# Sheet3.net
KiCad netlist of a schematic drawn in Altium Designer
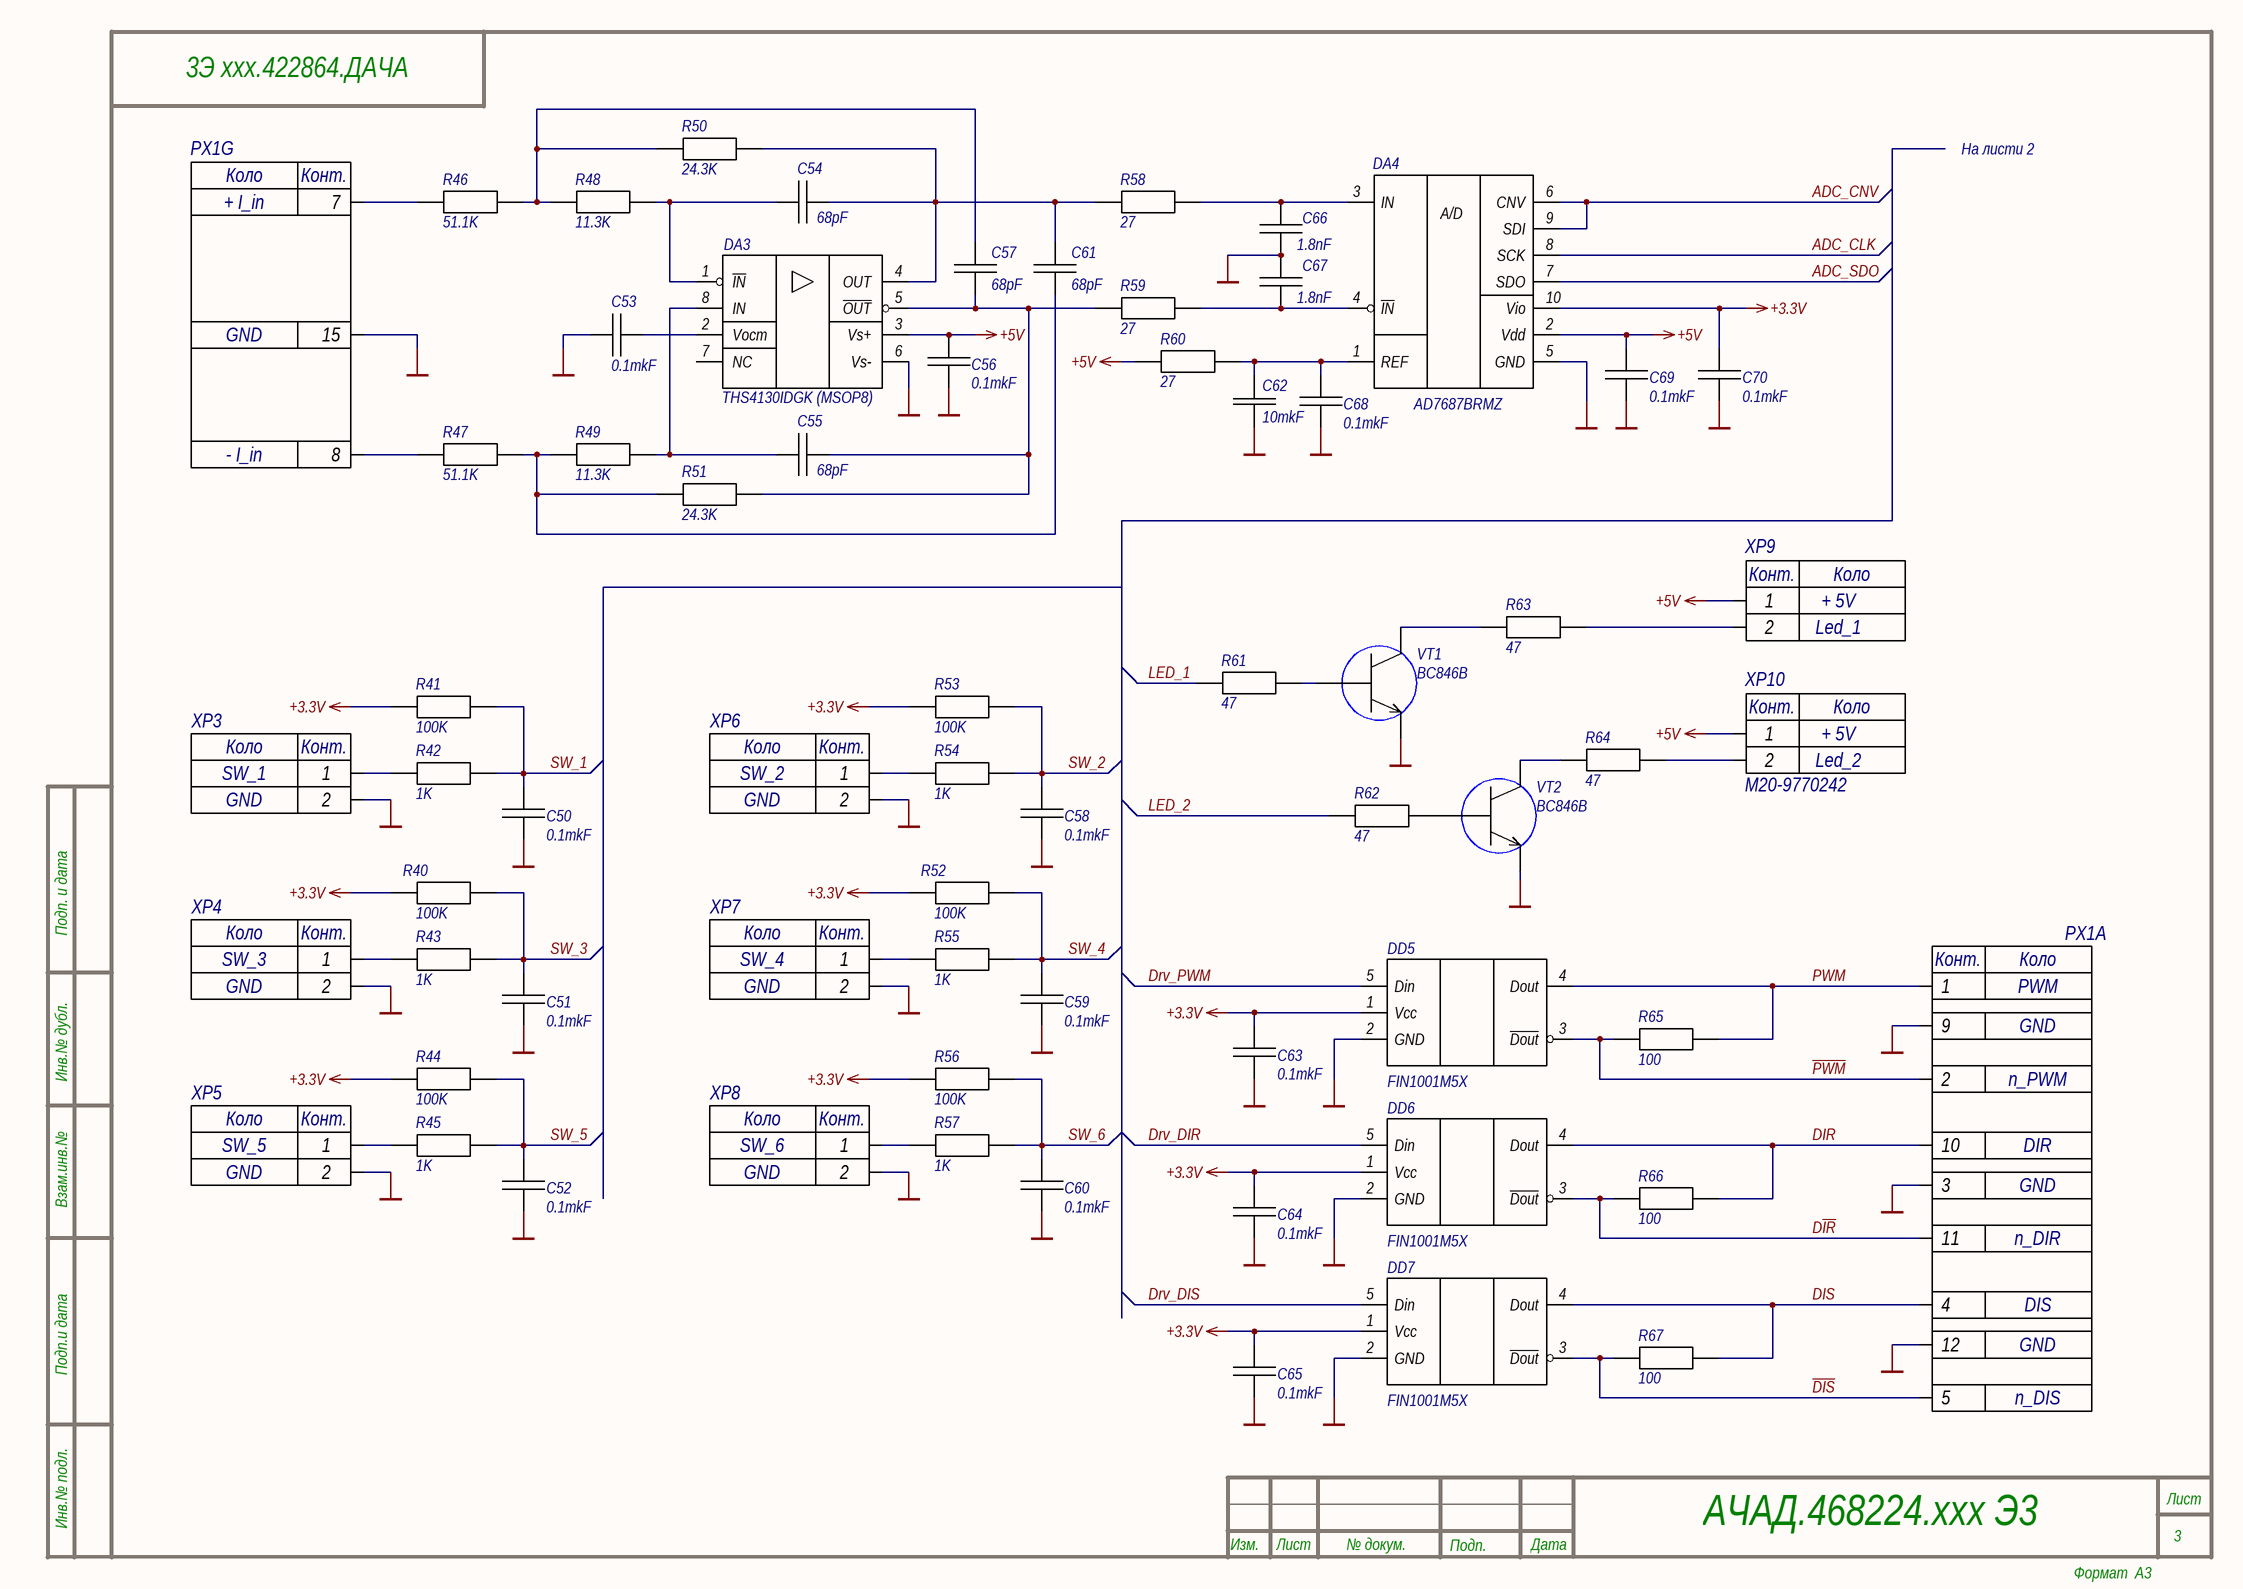
[diagram p0: Sheet3.SchDoc]

(export (version "E")
  (design (tool "Eeschema 10.0.6"))
  (components
    (comp (ref "C50")
      (value "0.1mkF")
      (footprint "C_0603")
      (description "C_0.1mkF_0603")
      (libsource (lib "АСК_1") (part "C_0.1mkF_0603"))
    )
    (comp (ref "C51")
      (value "0.1mkF")
      (footprint "C_0603")
      (description "C_0.1mkF_0603")
      (libsource (lib "АСК_1") (part "C_0.1mkF_0603"))
    )
    (comp (ref "C52")
      (value "0.1mkF")
      (footprint "C_0603")
      (description "C_0.1mkF_0603")
      (libsource (lib "АСК_1") (part "C_0.1mkF_0603"))
    )
    (comp (ref "C53")
      (value "0.1mkF")
      (footprint "C_0603")
      (description "C_0.1mkF_0603")
      (libsource (lib "АСК_1") (part "C_0.1mkF_0603"))
    )
    (comp (ref "C54")
      (value "68pF")
      (footprint "C_0603")
      (description "C_0.1mkF_0603")
      (libsource (lib "АСК_1") (part "C_0.1mkF_0603"))
    )
    (comp (ref "C55")
      (value "68pF")
      (footprint "C_0603")
      (description "C_0.1mkF_0603")
      (libsource (lib "АСК_1") (part "C_0.1mkF_0603"))
    )
    (comp (ref "C56")
      (value "0.1mkF")
      (footprint "C_0603")
      (description "C_0.1mkF_0603")
      (libsource (lib "АСК_1") (part "C_0.1mkF_0603"))
    )
    (comp (ref "C57")
      (value "68pF")
      (footprint "C_0603")
      (description "C_0.1mkF_0603")
      (libsource (lib "АСК_1") (part "C_0.1mkF_0603"))
    )
    (comp (ref "C58")
      (value "0.1mkF")
      (footprint "C_0603")
      (description "C_0.1mkF_0603")
      (libsource (lib "АСК_1") (part "C_0.1mkF_0603"))
    )
    (comp (ref "C59")
      (value "0.1mkF")
      (footprint "C_0603")
      (description "C_0.1mkF_0603")
      (libsource (lib "АСК_1") (part "C_0.1mkF_0603"))
    )
    (comp (ref "C60")
      (value "0.1mkF")
      (footprint "C_0603")
      (description "C_0.1mkF_0603")
      (libsource (lib "АСК_1") (part "C_0.1mkF_0603"))
    )
    (comp (ref "C61")
      (value "68pF")
      (footprint "C_0603")
      (description "C_0.1mkF_0603")
      (libsource (lib "АСК_1") (part "C_0.1mkF_0603"))
    )
    (comp (ref "C62")
      (value "10mkF")
      (footprint "C_1206")
      (description "C_10mkF_1206")
      (libsource (lib "АСК_1") (part "C_10mkF_1206"))
    )
    (comp (ref "C63")
      (value "0.1mkF")
      (footprint "C_0603")
      (description "C_0.1mkF_0603")
      (libsource (lib "АСК_1") (part "C_0.1mkF_0603"))
    )
    (comp (ref "C64")
      (value "0.1mkF")
      (footprint "C_0603")
      (description "C_0.1mkF_0603")
      (libsource (lib "АСК_1") (part "C_0.1mkF_0603"))
    )
    (comp (ref "C65")
      (value "0.1mkF")
      (footprint "C_0603")
      (description "C_0.1mkF_0603")
      (libsource (lib "АСК_1") (part "C_0.1mkF_0603"))
    )
    (comp (ref "C66")
      (value "1.8nF")
      (footprint "C_0603")
      (description "C_0.1mkF_0603")
      (libsource (lib "АСК_1") (part "C_0.1mkF_0603"))
    )
    (comp (ref "C67")
      (value "1.8nF")
      (footprint "C_0603")
      (description "C_0.1mkF_0603")
      (libsource (lib "АСК_1") (part "C_0.1mkF_0603"))
    )
    (comp (ref "C68")
      (value "0.1mkF")
      (footprint "C_0603")
      (description "C_0.1mkF_0603")
      (libsource (lib "АСК_1") (part "C_0.1mkF_0603"))
    )
    (comp (ref "C69")
      (value "0.1mkF")
      (footprint "C_0603")
      (description "C_0.1mkF_0603")
      (libsource (lib "АСК_1") (part "C_0.1mkF_0603"))
    )
    (comp (ref "C70")
      (value "0.1mkF")
      (footprint "C_0603")
      (description "C_0.1mkF_0603")
      (libsource (lib "АСК_1") (part "C_0.1mkF_0603"))
    )
    (comp (ref "DA3")
      (value "THS4130IDGK (MSOP8)")
      (footprint "THS4130IDGK(MSOP8)")
      (libsource (lib "АСК_1") (part "THS4130IDGK (MSOP8)"))
    )
    (comp (ref "DA4") (value "AD7687BRMZ") (libsource (lib "АСК_1") (part "AD7687BRMZ")))
    (comp (ref "DD5") (value "FIN1001M5X") (libsource (lib "АСК_1") (part "FIN1001M5X")))
    (comp (ref "DD6") (value "FIN1001M5X") (libsource (lib "АСК_1") (part "FIN1001M5X")))
    (comp (ref "DD7") (value "FIN1001M5X") (libsource (lib "АСК_1") (part "FIN1001M5X")))
    (comp (ref "PX1") (value "DB_15") (libsource (lib "АСК_1") (part "DB_15")))
    (comp (ref "R40")
      (value "100K")
      (footprint "R_0603")
      (description "R_100_0603")
      (libsource (lib "АСК_1") (part "R_100_0603"))
    )
    (comp (ref "R41")
      (value "100K")
      (footprint "R_0603")
      (description "R_100_0603")
      (libsource (lib "АСК_1") (part "R_100_0603"))
    )
    (comp (ref "R42")
      (value "1K")
      (footprint "R_0603")
      (description "R_100_0603")
      (libsource (lib "АСК_1") (part "R_100_0603"))
    )
    (comp (ref "R43")
      (value "1K")
      (footprint "R_0603")
      (description "R_100_0603")
      (libsource (lib "АСК_1") (part "R_100_0603"))
    )
    (comp (ref "R44")
      (value "100K")
      (footprint "R_0603")
      (description "R_100_0603")
      (libsource (lib "АСК_1") (part "R_100_0603"))
    )
    (comp (ref "R45")
      (value "1K")
      (footprint "R_0603")
      (description "R_100_0603")
      (libsource (lib "АСК_1") (part "R_100_0603"))
    )
    (comp (ref "R46")
      (value "51.1K")
      (footprint "R_0603")
      (description "R_100_0603")
      (libsource (lib "АСК_1") (part "R_100_0603"))
    )
    (comp (ref "R47")
      (value "51.1K")
      (footprint "R_0603")
      (description "R_100_0603")
      (libsource (lib "АСК_1") (part "R_100_0603"))
    )
    (comp (ref "R48")
      (value "11.3K")
      (footprint "R_0603")
      (description "R_100_0603")
      (libsource (lib "АСК_1") (part "R_100_0603"))
    )
    (comp (ref "R49")
      (value "11.3K")
      (footprint "R_0603")
      (description "R_100_0603")
      (libsource (lib "АСК_1") (part "R_100_0603"))
    )
    (comp (ref "R50")
      (value "24.3K")
      (footprint "R_0603")
      (description "R_100_0603")
      (libsource (lib "АСК_1") (part "R_100_0603"))
    )
    (comp (ref "R51")
      (value "24.3K")
      (footprint "R_0603")
      (description "R_100_0603")
      (libsource (lib "АСК_1") (part "R_100_0603"))
    )
    (comp (ref "R52")
      (value "100K")
      (footprint "R_0603")
      (description "R_100_0603")
      (libsource (lib "АСК_1") (part "R_100_0603"))
    )
    (comp (ref "R53")
      (value "100K")
      (footprint "R_0603")
      (description "R_100_0603")
      (libsource (lib "АСК_1") (part "R_100_0603"))
    )
    (comp (ref "R54")
      (value "1K")
      (footprint "R_0603")
      (description "R_100_0603")
      (libsource (lib "АСК_1") (part "R_100_0603"))
    )
    (comp (ref "R55")
      (value "1K")
      (footprint "R_0603")
      (description "R_100_0603")
      (libsource (lib "АСК_1") (part "R_100_0603"))
    )
    (comp (ref "R56")
      (value "100K")
      (footprint "R_0603")
      (description "R_100_0603")
      (libsource (lib "АСК_1") (part "R_100_0603"))
    )
    (comp (ref "R57")
      (value "1K")
      (footprint "R_0603")
      (description "R_100_0603")
      (libsource (lib "АСК_1") (part "R_100_0603"))
    )
    (comp (ref "R58")
      (value "27")
      (footprint "R_0603")
      (description "R_100_0603")
      (libsource (lib "АСК_1") (part "R_100_0603"))
    )
    (comp (ref "R59")
      (value "27")
      (footprint "R_0603")
      (description "R_100_0603")
      (libsource (lib "АСК_1") (part "R_100_0603"))
    )
    (comp (ref "R60")
      (value "27")
      (footprint "R_0603")
      (description "R_100_0603")
      (libsource (lib "АСК_1") (part "R_100_0603"))
    )
    (comp (ref "R61")
      (value "47")
      (footprint "R_0603")
      (description "R_100_0603")
      (libsource (lib "АСК_1") (part "R_100_0603"))
    )
    (comp (ref "R62")
      (value "47")
      (footprint "R_0603")
      (description "R_100_0603")
      (libsource (lib "АСК_1") (part "R_100_0603"))
    )
    (comp (ref "R63")
      (value "47")
      (footprint "R_0603")
      (description "R_100_0603")
      (libsource (lib "АСК_1") (part "R_100_0603"))
    )
    (comp (ref "R64")
      (value "47")
      (footprint "R_0603")
      (description "R_100_0603")
      (libsource (lib "АСК_1") (part "R_100_0603"))
    )
    (comp (ref "R65")
      (value "100")
      (footprint "R_0603")
      (description "R_100_0603")
      (libsource (lib "АСК_1") (part "R_100_0603"))
    )
    (comp (ref "R66")
      (value "100")
      (footprint "R_0603")
      (description "R_100_0603")
      (libsource (lib "АСК_1") (part "R_100_0603"))
    )
    (comp (ref "R67")
      (value "100")
      (footprint "R_0603")
      (description "R_100_0603")
      (libsource (lib "АСК_1") (part "R_100_0603"))
    )
    (comp (ref "VT1")
      (value "BC846B")
      (footprint "SOT95P245X110 3N")
      (libsource (lib "АСК_1") (part "BC846B"))
    )
    (comp (ref "VT2")
      (value "BC846B")
      (footprint "SOT95P245X110 3N")
      (libsource (lib "АСК_1") (part "BC846B"))
    )
    (comp (ref "XP3") (value "M20-9770242") (libsource (lib "АСК_1") (part "M20-9770242")))
    (comp (ref "XP4") (value "M20-9770242") (libsource (lib "АСК_1") (part "M20-9770242")))
    (comp (ref "XP5") (value "M20-9770242") (libsource (lib "АСК_1") (part "M20-9770242")))
    (comp (ref "XP6") (value "M20-9770242") (libsource (lib "АСК_1") (part "M20-9770242")))
    (comp (ref "XP7") (value "M20-9770242") (libsource (lib "АСК_1") (part "M20-9770242")))
    (comp (ref "XP8") (value "M20-9770242") (libsource (lib "АСК_1") (part "M20-9770242")))
    (comp (ref "XP9") (value "M20-9770242") (libsource (lib "АСК_1") (part "M20-9770242")))
    (comp (ref "XP10") (value "M20-9770242") (libsource (lib "АСК_1") (part "M20-9770242")))
  )
  (nets
    (net (code "1") (name "+3.3V") (class "Default")
      (node (ref "C63") (pin "1") (pinfunction "1_1") (pintype "passive"))
      (node (ref "C64") (pin "1") (pinfunction "1_1") (pintype "passive"))
      (node (ref "C65") (pin "1") (pinfunction "1_1") (pintype "passive"))
      (node (ref "C70") (pin "1") (pinfunction "1_1") (pintype "passive"))
      (node (ref "DA4") (pin "10") (pinfunction "Vio_10") (pintype "passive"))
      (node (ref "DD5") (pin "1") (pinfunction "Vcc_1") (pintype "passive"))
      (node (ref "DD6") (pin "1") (pinfunction "Vcc_1") (pintype "passive"))
      (node (ref "DD7") (pin "1") (pinfunction "Vcc_1") (pintype "passive"))
      (node (ref "R40") (pin "1") (pinfunction "1_1") (pintype "passive"))
      (node (ref "R41") (pin "1") (pinfunction "1_1") (pintype "passive"))
      (node (ref "R44") (pin "1") (pinfunction "1_1") (pintype "passive"))
      (node (ref "R52") (pin "1") (pinfunction "1_1") (pintype "passive"))
      (node (ref "R53") (pin "1") (pinfunction "1_1") (pintype "passive"))
      (node (ref "R56") (pin "1") (pinfunction "1_1") (pintype "passive"))
    )
    (net (code "2") (name "+5V") (class "Default")
      (node (ref "C56") (pin "1") (pinfunction "1_1") (pintype "passive"))
      (node (ref "C69") (pin "1") (pinfunction "1_1") (pintype "passive"))
      (node (ref "DA3") (pin "3") (pinfunction "Vs+_3") (pintype "passive"))
      (node (ref "DA4") (pin "2") (pinfunction "Vdd_2") (pintype "passive"))
      (node (ref "R60") (pin "1") (pinfunction "1_1") (pintype "passive"))
      (node (ref "XP10") (pin "1") (pinfunction "1_1") (pintype "passive"))
      (node (ref "XP9") (pin "1") (pinfunction "1_1") (pintype "passive"))
    )
    (net (code "3") (name "/ADC_CLK") (class "Default")
      (node (ref "DA4") (pin "8") (pinfunction "SCK_8") (pintype "passive"))
    )
    (net (code "4") (name "/ADC_CNV") (class "Default")
      (node (ref "DA4") (pin "6") (pinfunction "CNV_6") (pintype "passive"))
      (node (ref "DA4") (pin "9") (pinfunction "SDI_9") (pintype "passive"))
    )
    (net (code "5") (name "/ADC_SDO") (class "Default")
      (node (ref "DA4") (pin "7") (pinfunction "SDO_7") (pintype "passive"))
    )
    (net (code "6") (name "/DIR") (class "Default")
      (node (ref "DD6") (pin "4") (pinfunction "Dout_4") (pintype "passive"))
      (node (ref "PX1") (pin "10") (pinfunction "10_10") (pintype "passive"))
      (node (ref "R66") (pin "2") (pinfunction "2_2") (pintype "passive"))
    )
    (net (code "7") (name "/DIS") (class "Default")
      (node (ref "DD7") (pin "4") (pinfunction "Dout_4") (pintype "passive"))
      (node (ref "PX1") (pin "4") (pinfunction "4_4") (pintype "passive"))
      (node (ref "R67") (pin "2") (pinfunction "2_2") (pintype "passive"))
    )
    (net (code "8") (name "/Drv_DIR") (class "Default")
      (node (ref "DD6") (pin "5") (pinfunction "Din_5") (pintype "passive"))
    )
    (net (code "9") (name "/Drv_DIS") (class "Default")
      (node (ref "DD7") (pin "5") (pinfunction "Din_5") (pintype "passive"))
    )
    (net (code "10") (name "/Drv_PWM") (class "Default")
      (node (ref "DD5") (pin "5") (pinfunction "Din_5") (pintype "passive"))
    )
    (net (code "11") (name "/D~{IR}") (class "Default")
      (node (ref "DD6") (pin "3") (pinfunction "~{Dout}_3") (pintype "passive"))
      (node (ref "PX1") (pin "11") (pinfunction "11_11") (pintype "passive"))
      (node (ref "R66") (pin "1") (pinfunction "1_1") (pintype "passive"))
    )
    (net (code "12") (name "/LED_1") (class "Default")
      (node (ref "R61") (pin "1") (pinfunction "1_1") (pintype "passive"))
    )
    (net (code "13") (name "/LED_2") (class "Default")
      (node (ref "R62") (pin "1") (pinfunction "1_1") (pintype "passive"))
    )
    (net (code "14") (name "/PWM") (class "Default")
      (node (ref "DD5") (pin "4") (pinfunction "Dout_4") (pintype "passive"))
      (node (ref "PX1") (pin "1") (pinfunction "1_1") (pintype "passive"))
      (node (ref "R65") (pin "2") (pinfunction "2_2") (pintype "passive"))
    )
    (net (code "15") (name "/SW_1") (class "Default")
      (node (ref "C50") (pin "1") (pinfunction "1_1") (pintype "passive"))
      (node (ref "R41") (pin "2") (pinfunction "2_2") (pintype "passive"))
      (node (ref "R42") (pin "2") (pinfunction "2_2") (pintype "passive"))
    )
    (net (code "16") (name "/SW_2") (class "Default")
      (node (ref "C58") (pin "1") (pinfunction "1_1") (pintype "passive"))
      (node (ref "R53") (pin "2") (pinfunction "2_2") (pintype "passive"))
      (node (ref "R54") (pin "2") (pinfunction "2_2") (pintype "passive"))
    )
    (net (code "17") (name "/SW_3") (class "Default")
      (node (ref "C51") (pin "1") (pinfunction "1_1") (pintype "passive"))
      (node (ref "R40") (pin "2") (pinfunction "2_2") (pintype "passive"))
      (node (ref "R43") (pin "2") (pinfunction "2_2") (pintype "passive"))
    )
    (net (code "18") (name "/SW_4") (class "Default")
      (node (ref "C59") (pin "1") (pinfunction "1_1") (pintype "passive"))
      (node (ref "R52") (pin "2") (pinfunction "2_2") (pintype "passive"))
      (node (ref "R55") (pin "2") (pinfunction "2_2") (pintype "passive"))
    )
    (net (code "19") (name "/SW_5") (class "Default")
      (node (ref "C52") (pin "1") (pinfunction "1_1") (pintype "passive"))
      (node (ref "R44") (pin "2") (pinfunction "2_2") (pintype "passive"))
      (node (ref "R45") (pin "2") (pinfunction "2_2") (pintype "passive"))
    )
    (net (code "20") (name "/SW_6") (class "Default")
      (node (ref "C60") (pin "1") (pinfunction "1_1") (pintype "passive"))
      (node (ref "R56") (pin "2") (pinfunction "2_2") (pintype "passive"))
      (node (ref "R57") (pin "2") (pinfunction "2_2") (pintype "passive"))
    )
    (net (code "21") (name "/~{DIS}") (class "Default")
      (node (ref "DD7") (pin "3") (pinfunction "~{Dout}_3") (pintype "passive"))
      (node (ref "PX1") (pin "5") (pinfunction "5_5") (pintype "passive"))
      (node (ref "R67") (pin "1") (pinfunction "1_1") (pintype "passive"))
    )
    (net (code "22") (name "/~{PWM}") (class "Default")
      (node (ref "DD5") (pin "3") (pinfunction "~{Dout}_3") (pintype "passive"))
      (node (ref "PX1") (pin "1") (pinfunction "2_1") (pintype "passive"))
      (node (ref "R65") (pin "1") (pinfunction "1_1") (pintype "passive"))
    )
    (net (code "23") (name "GND") (class "Default")
      (node (ref "C50") (pin "2") (pinfunction "2_2") (pintype "passive"))
      (node (ref "C51") (pin "2") (pinfunction "2_2") (pintype "passive"))
      (node (ref "C52") (pin "2") (pinfunction "2_2") (pintype "passive"))
      (node (ref "C53") (pin "1") (pinfunction "1_1") (pintype "passive"))
      (node (ref "C56") (pin "2") (pinfunction "2_2") (pintype "passive"))
      (node (ref "C58") (pin "2") (pinfunction "2_2") (pintype "passive"))
      (node (ref "C59") (pin "2") (pinfunction "2_2") (pintype "passive"))
      (node (ref "C60") (pin "2") (pinfunction "2_2") (pintype "passive"))
      (node (ref "C62") (pin "1") (pinfunction "1_1") (pintype "passive"))
      (node (ref "C63") (pin "2") (pinfunction "2_2") (pintype "passive"))
      (node (ref "C64") (pin "2") (pinfunction "2_2") (pintype "passive"))
      (node (ref "C65") (pin "2") (pinfunction "2_2") (pintype "passive"))
      (node (ref "C66") (pin "2") (pinfunction "2_2") (pintype "passive"))
      (node (ref "C67") (pin "1") (pinfunction "1_1") (pintype "passive"))
      (node (ref "C68") (pin "2") (pinfunction "2_2") (pintype "passive"))
      (node (ref "C69") (pin "2") (pinfunction "2_2") (pintype "passive"))
      (node (ref "C70") (pin "2") (pinfunction "2_2") (pintype "passive"))
      (node (ref "DA3") (pin "6") (pinfunction "Vs-_6") (pintype "passive"))
      (node (ref "DA4") (pin "5") (pinfunction "GND_5") (pintype "passive"))
      (node (ref "DD5") (pin "2") (pinfunction "GND_2") (pintype "passive"))
      (node (ref "DD6") (pin "2") (pinfunction "GND_2") (pintype "passive"))
      (node (ref "DD7") (pin "2") (pinfunction "GND_2") (pintype "passive"))
      (node (ref "PX1") (pin "12") (pinfunction "12_12") (pintype "passive"))
      (node (ref "PX1") (pin "15") (pinfunction "15_15") (pintype "passive"))
      (node (ref "PX1") (pin "3") (pinfunction "3_3") (pintype "passive"))
      (node (ref "PX1") (pin "9") (pinfunction "9_9") (pintype "passive"))
      (node (ref "VT1") (pin "2") (pinfunction "2_2") (pintype "passive"))
      (node (ref "VT2") (pin "2") (pinfunction "2_2") (pintype "passive"))
      (node (ref "XP3") (pin "2") (pinfunction "2_2") (pintype "passive"))
      (node (ref "XP4") (pin "2") (pinfunction "2_2") (pintype "passive"))
      (node (ref "XP5") (pin "2") (pinfunction "2_2") (pintype "passive"))
      (node (ref "XP6") (pin "2") (pinfunction "2_2") (pintype "passive"))
      (node (ref "XP7") (pin "2") (pinfunction "2_2") (pintype "passive"))
      (node (ref "XP8") (pin "2") (pinfunction "2_2") (pintype "passive"))
    )
    (net (code "24") (name "Net-(C57-Pad1)") (class "Default")
      (node (ref "C57") (pin "1") (pinfunction "1_1") (pintype "passive"))
      (node (ref "R46") (pin "2") (pinfunction "2_2") (pintype "passive"))
      (node (ref "R48") (pin "1") (pinfunction "1_1") (pintype "passive"))
      (node (ref "R50") (pin "1") (pinfunction "1_1") (pintype "passive"))
    )
    (net (code "25") (name "Net-(C61-Pad2)") (class "Default")
      (node (ref "C61") (pin "2") (pinfunction "2_2") (pintype "passive"))
      (node (ref "R47") (pin "2") (pinfunction "2_2") (pintype "passive"))
      (node (ref "R49") (pin "2") (pinfunction "2_2") (pintype "passive"))
      (node (ref "R51") (pin "2") (pinfunction "2_2") (pintype "passive"))
    )
    (net (code "26") (name "Net-(DA3-IN)") (class "Default")
      (node (ref "C55") (pin "2") (pinfunction "2_2") (pintype "passive"))
      (node (ref "DA3") (pin "8") (pinfunction "IN_8") (pintype "passive"))
      (node (ref "R49") (pin "1") (pinfunction "1_1") (pintype "passive"))
    )
    (net (code "27") (name "Net-(DA3-OUT)") (class "Default")
      (node (ref "C54") (pin "1") (pinfunction "1_1") (pintype "passive"))
      (node (ref "C61") (pin "1") (pinfunction "1_1") (pintype "passive"))
      (node (ref "DA3") (pin "4") (pinfunction "OUT_4") (pintype "passive"))
      (node (ref "R50") (pin "2") (pinfunction "2_2") (pintype "passive"))
      (node (ref "R58") (pin "1") (pinfunction "1_1") (pintype "passive"))
    )
    (net (code "28") (name "Net-(DA3-Vocm)") (class "Default")
      (node (ref "C53") (pin "2") (pinfunction "2_2") (pintype "passive"))
      (node (ref "DA3") (pin "2") (pinfunction "Vocm_2") (pintype "passive"))
    )
    (net (code "29") (name "Net-(DA3-~{IN})") (class "Default")
      (node (ref "C54") (pin "2") (pinfunction "2_2") (pintype "passive"))
      (node (ref "DA3") (pin "1") (pinfunction "~{IN}_1") (pintype "passive"))
      (node (ref "R48") (pin "2") (pinfunction "2_2") (pintype "passive"))
    )
    (net (code "30") (name "Net-(DA3-~{OUT})") (class "Default")
      (node (ref "C55") (pin "1") (pinfunction "1_1") (pintype "passive"))
      (node (ref "C57") (pin "2") (pinfunction "2_2") (pintype "passive"))
      (node (ref "DA3") (pin "5") (pinfunction "~{OUT}_5") (pintype "passive"))
      (node (ref "R51") (pin "1") (pinfunction "1_1") (pintype "passive"))
      (node (ref "R59") (pin "1") (pinfunction "1_1") (pintype "passive"))
    )
    (net (code "31") (name "Net-(DA4-IN)") (class "Default")
      (node (ref "C66") (pin "1") (pinfunction "1_1") (pintype "passive"))
      (node (ref "DA4") (pin "3") (pinfunction "IN_3") (pintype "passive"))
      (node (ref "R58") (pin "2") (pinfunction "2_2") (pintype "passive"))
    )
    (net (code "32") (name "Net-(DA4-REF)") (class "Default")
      (node (ref "C62") (pin "2") (pinfunction "2_2") (pintype "passive"))
      (node (ref "C68") (pin "1") (pinfunction "1_1") (pintype "passive"))
      (node (ref "DA4") (pin "1") (pinfunction "REF_1") (pintype "passive"))
      (node (ref "R60") (pin "2") (pinfunction "2_2") (pintype "passive"))
    )
    (net (code "33") (name "Net-(DA4-~{IN})") (class "Default")
      (node (ref "C67") (pin "2") (pinfunction "2_2") (pintype "passive"))
      (node (ref "DA4") (pin "4") (pinfunction "~{IN}_4") (pintype "passive"))
      (node (ref "R59") (pin "2") (pinfunction "2_2") (pintype "passive"))
    )
    (net (code "34") (name "Net-(PX1-Pad7)") (class "Default")
      (node (ref "PX1") (pin "7") (pinfunction "7_7") (pintype "passive"))
      (node (ref "R46") (pin "1") (pinfunction "1_1") (pintype "passive"))
    )
    (net (code "35") (name "Net-(PX1-Pad8)") (class "Default")
      (node (ref "PX1") (pin "8") (pinfunction "8_8") (pintype "passive"))
      (node (ref "R47") (pin "1") (pinfunction "1_1") (pintype "passive"))
    )
    (net (code "36") (name "Net-(R42-Pad1)") (class "Default")
      (node (ref "R42") (pin "1") (pinfunction "1_1") (pintype "passive"))
      (node (ref "XP3") (pin "1") (pinfunction "1_1") (pintype "passive"))
    )
    (net (code "37") (name "Net-(R43-Pad1)") (class "Default")
      (node (ref "R43") (pin "1") (pinfunction "1_1") (pintype "passive"))
      (node (ref "XP4") (pin "1") (pinfunction "1_1") (pintype "passive"))
    )
    (net (code "38") (name "Net-(R45-Pad1)") (class "Default")
      (node (ref "R45") (pin "1") (pinfunction "1_1") (pintype "passive"))
      (node (ref "XP5") (pin "1") (pinfunction "1_1") (pintype "passive"))
    )
    (net (code "39") (name "Net-(R54-Pad1)") (class "Default")
      (node (ref "R54") (pin "1") (pinfunction "1_1") (pintype "passive"))
      (node (ref "XP6") (pin "1") (pinfunction "1_1") (pintype "passive"))
    )
    (net (code "40") (name "Net-(R55-Pad1)") (class "Default")
      (node (ref "R55") (pin "1") (pinfunction "1_1") (pintype "passive"))
      (node (ref "XP7") (pin "1") (pinfunction "1_1") (pintype "passive"))
    )
    (net (code "41") (name "Net-(R57-Pad1)") (class "Default")
      (node (ref "R57") (pin "1") (pinfunction "1_1") (pintype "passive"))
      (node (ref "XP8") (pin "1") (pinfunction "1_1") (pintype "passive"))
    )
    (net (code "42") (name "Net-(R61-Pad2)") (class "Default")
      (node (ref "R61") (pin "2") (pinfunction "2_2") (pintype "passive"))
      (node (ref "VT1") (pin "1") (pinfunction "1_1") (pintype "passive"))
    )
    (net (code "43") (name "Net-(R62-Pad2)") (class "Default")
      (node (ref "R62") (pin "2") (pinfunction "2_2") (pintype "passive"))
      (node (ref "VT2") (pin "1") (pinfunction "1_1") (pintype "passive"))
    )
    (net (code "44") (name "Net-(R63-Pad1)") (class "Default")
      (node (ref "R63") (pin "1") (pinfunction "1_1") (pintype "passive"))
      (node (ref "VT1") (pin "3") (pinfunction "3_3") (pintype "passive"))
    )
    (net (code "45") (name "Net-(R63-Pad2)") (class "Default")
      (node (ref "R63") (pin "2") (pinfunction "2_2") (pintype "passive"))
      (node (ref "XP9") (pin "2") (pinfunction "2_2") (pintype "passive"))
    )
    (net (code "46") (name "Net-(R64-Pad1)") (class "Default")
      (node (ref "R64") (pin "1") (pinfunction "1_1") (pintype "passive"))
      (node (ref "VT2") (pin "3") (pinfunction "3_3") (pintype "passive"))
    )
    (net (code "47") (name "Net-(R64-Pad2)") (class "Default")
      (node (ref "R64") (pin "2") (pinfunction "2_2") (pintype "passive"))
      (node (ref "XP10") (pin "2") (pinfunction "2_2") (pintype "passive"))
    )
    (net (code "48") (name "unconnected-(DA3-NC-Pad7)") (class "Default")
      (node (ref "DA3") (pin "7") (pinfunction "NC_7") (pintype "passive"))
    )
  )
)
